# MultiGRADE_control_panel_V01_R1.net
KiCad netlist of a schematic drawn in EAGLE
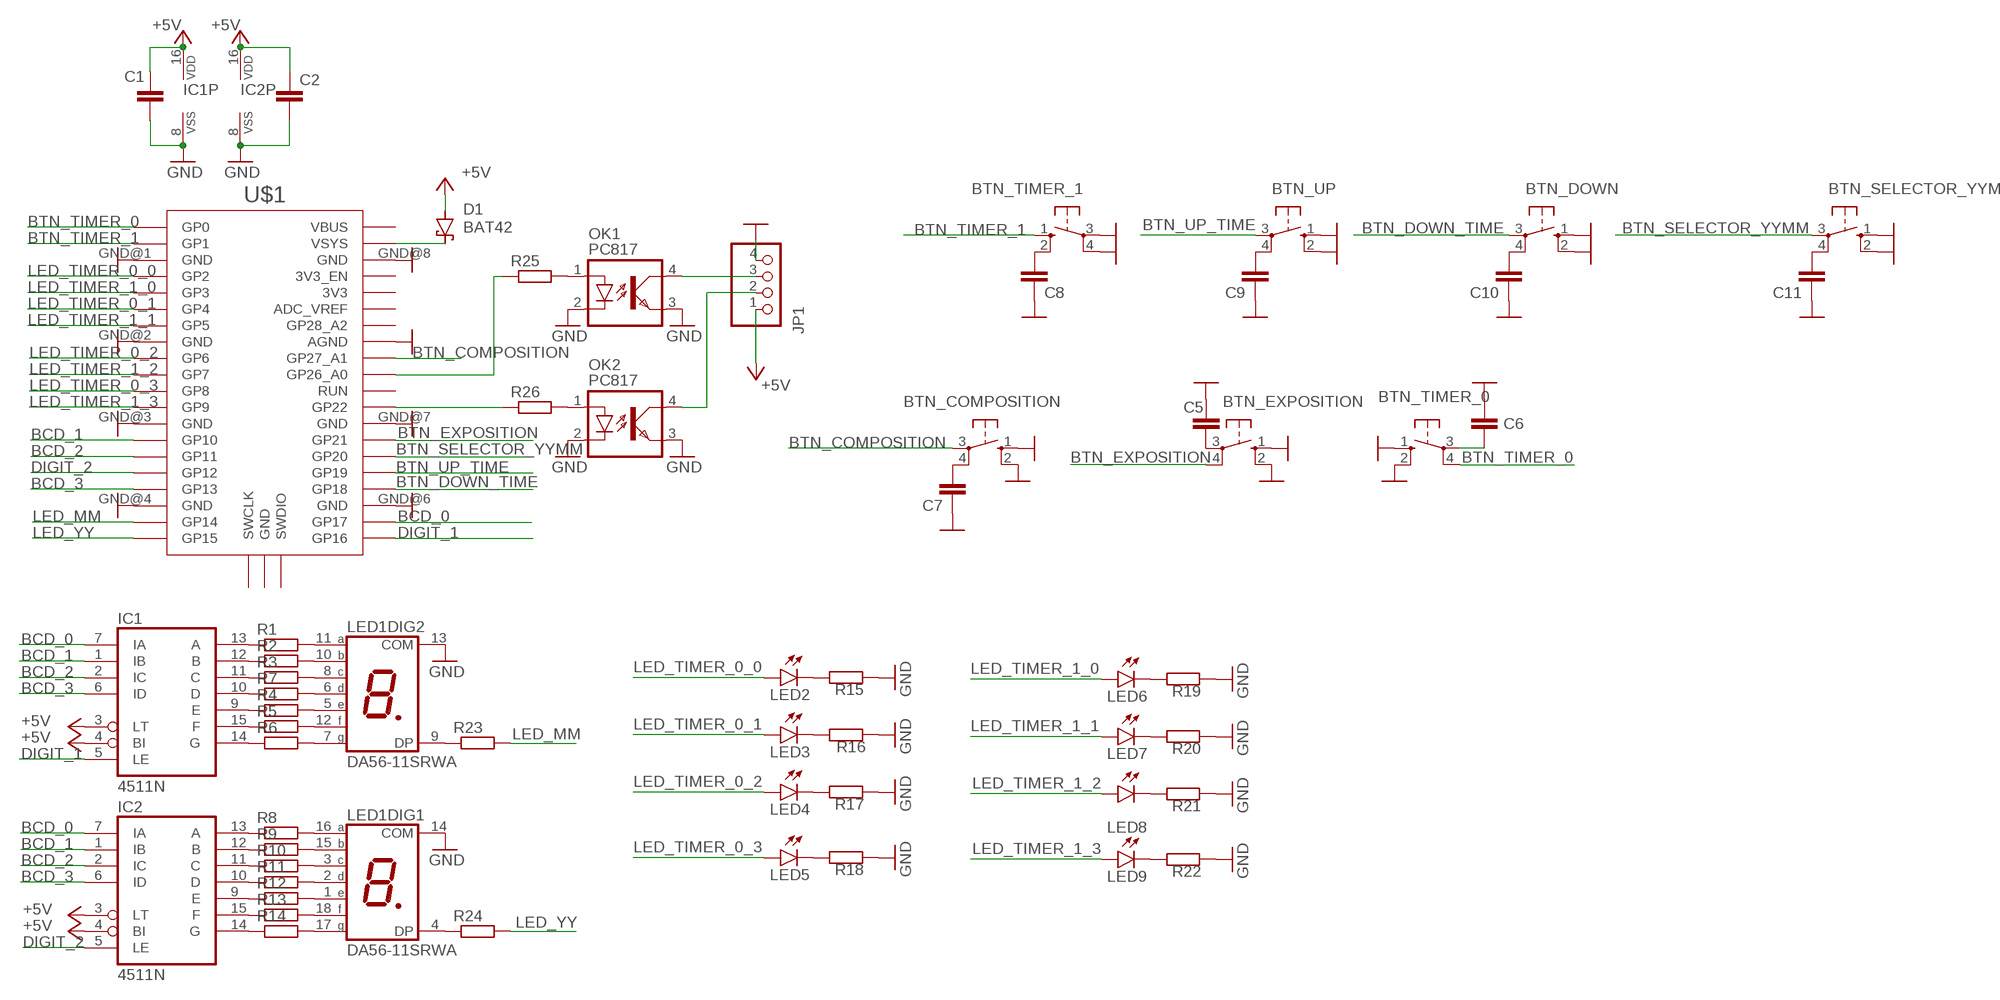
[diagram p0: schematic, sheet 1]

(export (version "E")
  (design (tool "Eeschema 10.0.6"))
  (components
    (comp (ref "BTN_COMPOSITION")
      (value "10-XX")
      (footprint "eagle-import:B3F-10XX")
      (fields (field (name "MPN") "B3F-1000"))
      (libsource (lib "eagle-import") (part "10-XX"))
    )
    (comp (ref "BTN_DOWN")
      (value "10-XX")
      (footprint "eagle-import:B3F-10XX")
      (fields (field (name "MPN") "B3F-1000"))
      (libsource (lib "eagle-import") (part "10-XX"))
    )
    (comp (ref "BTN_EXPOSITION")
      (value "10-XX")
      (footprint "eagle-import:B3F-10XX")
      (fields (field (name "MPN") "B3F-1000"))
      (libsource (lib "eagle-import") (part "10-XX"))
    )
    (comp (ref "BTN_SELECTOR_YYMM")
      (value "10-XX")
      (footprint "eagle-import:B3F-10XX")
      (fields (field (name "MPN") "B3F-1000"))
      (libsource (lib "eagle-import") (part "10-XX"))
    )
    (comp (ref "BTN_TIMER_0")
      (value "10-XX")
      (footprint "eagle-import:B3F-10XX")
      (fields (field (name "MPN") "B3F-1000"))
      (libsource (lib "eagle-import") (part "10-XX"))
    )
    (comp (ref "BTN_TIMER_1")
      (value "10-XX")
      (footprint "eagle-import:B3F-10XX")
      (fields (field (name "MPN") "B3F-1000"))
      (libsource (lib "eagle-import") (part "10-XX"))
    )
    (comp (ref "BTN_UP")
      (value "10-XX")
      (footprint "eagle-import:B3F-10XX")
      (fields (field (name "MPN") "B3F-1000"))
      (libsource (lib "eagle-import") (part "10-XX"))
    )
    (comp (ref "C1")
      (value "C-EU050-025X075")
      (footprint "eagle-import:C050-025X075")
      (libsource (lib "eagle-import") (part "C-EU050-025X075"))
    )
    (comp (ref "C2")
      (value "C-EU050-025X075")
      (footprint "eagle-import:C050-025X075")
      (libsource (lib "eagle-import") (part "C-EU050-025X075"))
    )
    (comp (ref "C5")
      (value "C-EU025-025X050")
      (footprint "eagle-import:C025-025X050")
      (libsource (lib "eagle-import") (part "C-EU025-025X050"))
    )
    (comp (ref "C6")
      (value "C-EU025-025X050")
      (footprint "eagle-import:C025-025X050")
      (libsource (lib "eagle-import") (part "C-EU025-025X050"))
    )
    (comp (ref "C7")
      (value "C-EU025-025X050")
      (footprint "eagle-import:C025-025X050")
      (libsource (lib "eagle-import") (part "C-EU025-025X050"))
    )
    (comp (ref "C8")
      (value "C-EU025-025X050")
      (footprint "eagle-import:C025-025X050")
      (libsource (lib "eagle-import") (part "C-EU025-025X050"))
    )
    (comp (ref "C9")
      (value "C-EU025-025X050")
      (footprint "eagle-import:C025-025X050")
      (libsource (lib "eagle-import") (part "C-EU025-025X050"))
    )
    (comp (ref "C10")
      (value "C-EU025-025X050")
      (footprint "eagle-import:C025-025X050")
      (libsource (lib "eagle-import") (part "C-EU025-025X050"))
    )
    (comp (ref "C11")
      (value "C-EU025-025X050")
      (footprint "eagle-import:C025-025X050")
      (libsource (lib "eagle-import") (part "C-EU025-025X050"))
    )
    (comp (ref "D1")
      (value "BAT42")
      (footprint "eagle-import:DO35-10")
      (libsource (lib "eagle-import") (part "BAT42"))
    )
    (comp (ref "IC1")
      (value "4511N")
      (footprint "eagle-import:DIL16")
      (libsource (lib "eagle-import") (part "4511N"))
    )
    (comp (ref "IC2")
      (value "4511N")
      (footprint "eagle-import:DIL16")
      (libsource (lib "eagle-import") (part "4511N"))
    )
    (comp (ref "JP1")
      (value "PINHD-1X4")
      (footprint "eagle-import:1X04")
      (libsource (lib "eagle-import") (part "PINHD-1X4"))
    )
    (comp (ref "LED1")
      (value "DA56-11SRWA")
      (footprint "eagle-import:DA56")
      (libsource (lib "eagle-import") (part "DA56-11SRWA"))
    )
    (comp (ref "LED2")
      (value "LED3MM")
      (footprint "eagle-import:LED3MM")
      (libsource (lib "eagle-import") (part "LED3MM"))
    )
    (comp (ref "LED3")
      (value "LED3MM")
      (footprint "eagle-import:LED3MM")
      (libsource (lib "eagle-import") (part "LED3MM"))
    )
    (comp (ref "LED4")
      (value "LED3MM")
      (footprint "eagle-import:LED3MM")
      (libsource (lib "eagle-import") (part "LED3MM"))
    )
    (comp (ref "LED5")
      (value "LED3MM")
      (footprint "eagle-import:LED3MM")
      (libsource (lib "eagle-import") (part "LED3MM"))
    )
    (comp (ref "LED6")
      (value "LED3MM")
      (footprint "eagle-import:LED3MM")
      (libsource (lib "eagle-import") (part "LED3MM"))
    )
    (comp (ref "LED7")
      (value "LED3MM")
      (footprint "eagle-import:LED3MM")
      (libsource (lib "eagle-import") (part "LED3MM"))
    )
    (comp (ref "LED8")
      (value "LED3MM")
      (footprint "eagle-import:LED3MM")
      (libsource (lib "eagle-import") (part "LED3MM"))
    )
    (comp (ref "LED9")
      (value "LED3MM")
      (footprint "eagle-import:LED3MM")
      (libsource (lib "eagle-import") (part "LED3MM"))
    )
    (comp (ref "OK1")
      (value "PC817")
      (footprint "eagle-import:DIL04")
      (fields (field (name "MPN") "PC817X4J000F"))
      (libsource (lib "eagle-import") (part "PC817"))
    )
    (comp (ref "OK2")
      (value "PC817")
      (footprint "eagle-import:DIL04")
      (fields (field (name "MPN") "PC817X4J000F"))
      (libsource (lib "eagle-import") (part "PC817"))
    )
    (comp (ref "R1")
      (value "R-EU_0204/7")
      (footprint "eagle-import:0204_7")
      (libsource (lib "eagle-import") (part "R-EU_0204/7"))
    )
    (comp (ref "R2")
      (value "R-EU_0204/7")
      (footprint "eagle-import:0204_7")
      (libsource (lib "eagle-import") (part "R-EU_0204/7"))
    )
    (comp (ref "R3")
      (value "R-EU_0204/7")
      (footprint "eagle-import:0204_7")
      (libsource (lib "eagle-import") (part "R-EU_0204/7"))
    )
    (comp (ref "R4")
      (value "R-EU_0204/7")
      (footprint "eagle-import:0204_7")
      (libsource (lib "eagle-import") (part "R-EU_0204/7"))
    )
    (comp (ref "R5")
      (value "R-EU_0204/7")
      (footprint "eagle-import:0204_7")
      (libsource (lib "eagle-import") (part "R-EU_0204/7"))
    )
    (comp (ref "R6")
      (value "R-EU_0204/7")
      (footprint "eagle-import:0204_7")
      (libsource (lib "eagle-import") (part "R-EU_0204/7"))
    )
    (comp (ref "R7")
      (value "R-EU_0204/7")
      (footprint "eagle-import:0204_7")
      (libsource (lib "eagle-import") (part "R-EU_0204/7"))
    )
    (comp (ref "R8")
      (value "R-EU_0204/7")
      (footprint "eagle-import:0204_7")
      (libsource (lib "eagle-import") (part "R-EU_0204/7"))
    )
    (comp (ref "R9")
      (value "R-EU_0204/7")
      (footprint "eagle-import:0204_7")
      (libsource (lib "eagle-import") (part "R-EU_0204/7"))
    )
    (comp (ref "R10")
      (value "R-EU_0204/7")
      (footprint "eagle-import:0204_7")
      (libsource (lib "eagle-import") (part "R-EU_0204/7"))
    )
    (comp (ref "R11")
      (value "R-EU_0204/7")
      (footprint "eagle-import:0204_7")
      (libsource (lib "eagle-import") (part "R-EU_0204/7"))
    )
    (comp (ref "R12")
      (value "R-EU_0204/7")
      (footprint "eagle-import:0204_7")
      (libsource (lib "eagle-import") (part "R-EU_0204/7"))
    )
    (comp (ref "R13")
      (value "R-EU_0204/7")
      (footprint "eagle-import:0204_7")
      (libsource (lib "eagle-import") (part "R-EU_0204/7"))
    )
    (comp (ref "R14")
      (value "R-EU_0204/7")
      (footprint "eagle-import:0204_7")
      (libsource (lib "eagle-import") (part "R-EU_0204/7"))
    )
    (comp (ref "R15")
      (value "R-EU_0204/7")
      (footprint "eagle-import:0204_7")
      (libsource (lib "eagle-import") (part "R-EU_0204/7"))
    )
    (comp (ref "R16")
      (value "R-EU_0204/7")
      (footprint "eagle-import:0204_7")
      (libsource (lib "eagle-import") (part "R-EU_0204/7"))
    )
    (comp (ref "R17")
      (value "R-EU_0204/7")
      (footprint "eagle-import:0204_7")
      (libsource (lib "eagle-import") (part "R-EU_0204/7"))
    )
    (comp (ref "R18")
      (value "R-EU_0204/7")
      (footprint "eagle-import:0204_7")
      (libsource (lib "eagle-import") (part "R-EU_0204/7"))
    )
    (comp (ref "R19")
      (value "R-EU_0204/7")
      (footprint "eagle-import:0204_7")
      (libsource (lib "eagle-import") (part "R-EU_0204/7"))
    )
    (comp (ref "R20")
      (value "R-EU_0204/7")
      (footprint "eagle-import:0204_7")
      (libsource (lib "eagle-import") (part "R-EU_0204/7"))
    )
    (comp (ref "R21")
      (value "R-EU_0204/7")
      (footprint "eagle-import:0204_7")
      (libsource (lib "eagle-import") (part "R-EU_0204/7"))
    )
    (comp (ref "R22")
      (value "R-EU_0204/7")
      (footprint "eagle-import:0204_7")
      (libsource (lib "eagle-import") (part "R-EU_0204/7"))
    )
    (comp (ref "R23")
      (value "R-EU_0204/7")
      (footprint "eagle-import:0204_7")
      (libsource (lib "eagle-import") (part "R-EU_0204/7"))
    )
    (comp (ref "R24")
      (value "R-EU_0204/7")
      (footprint "eagle-import:0204_7")
      (libsource (lib "eagle-import") (part "R-EU_0204/7"))
    )
    (comp (ref "R25")
      (value "R-EU_0204/7")
      (footprint "eagle-import:0204_7")
      (libsource (lib "eagle-import") (part "R-EU_0204/7"))
    )
    (comp (ref "R26")
      (value "R-EU_0204/7")
      (footprint "eagle-import:0204_7")
      (libsource (lib "eagle-import") (part "R-EU_0204/7"))
    )
    (comp (ref "U$1")
      (value "RPI_PICO_IG-TH")
      (footprint "eagle-import:RPI_PICO_TH")
      (libsource (lib "eagle-import") (part "RPI_PICO_IG-TH"))
    )
  )
  (nets
    (net (code "1") (name "+5V") (class "Default")
      (node (ref "C1") (pin "1") (pinfunction "1_1") (pintype "passive"))
      (node (ref "C2") (pin "1") (pinfunction "1_1") (pintype "passive"))
      (node (ref "D1") (pin "A") (pinfunction "A_A") (pintype "passive"))
      (node (ref "IC1") (pin "16") (pinfunction "VDD_16") (pintype "power_in"))
      (node (ref "IC1") (pin "3") (pinfunction "LT_3") (pintype "input"))
      (node (ref "IC1") (pin "4") (pinfunction "BI_4") (pintype "input"))
      (node (ref "IC2") (pin "16") (pinfunction "VDD_16") (pintype "power_in"))
      (node (ref "IC2") (pin "3") (pinfunction "LT_3") (pintype "input"))
      (node (ref "IC2") (pin "4") (pinfunction "BI_4") (pintype "input"))
      (node (ref "JP1") (pin "1") (pinfunction "1_1") (pintype "passive"))
    )
    (net (code "2") (name "/BCD_0") (class "Default")
      (node (ref "IC1") (pin "7") (pinfunction "IA_7") (pintype "input"))
      (node (ref "IC2") (pin "7") (pinfunction "IA_7") (pintype "input"))
      (node (ref "U$1") (pin "GP17") (pinfunction "GP17_GP17") (pintype "bidirectional"))
    )
    (net (code "3") (name "/BCD_1") (class "Default")
      (node (ref "IC1") (pin "1") (pinfunction "IB_1") (pintype "input"))
      (node (ref "IC2") (pin "1") (pinfunction "IB_1") (pintype "input"))
      (node (ref "U$1") (pin "GP10") (pinfunction "GP10_GP10") (pintype "bidirectional"))
    )
    (net (code "4") (name "/BCD_2") (class "Default")
      (node (ref "IC1") (pin "2") (pinfunction "IC_2") (pintype "input"))
      (node (ref "IC2") (pin "2") (pinfunction "IC_2") (pintype "input"))
      (node (ref "U$1") (pin "GP11") (pinfunction "GP11_GP11") (pintype "bidirectional"))
    )
    (net (code "5") (name "/BCD_3") (class "Default")
      (node (ref "IC1") (pin "6") (pinfunction "ID_6") (pintype "input"))
      (node (ref "IC2") (pin "6") (pinfunction "ID_6") (pintype "input"))
      (node (ref "U$1") (pin "GP13") (pinfunction "GP13_GP13") (pintype "bidirectional"))
    )
    (net (code "6") (name "/BTN_COMPOSITION") (class "Default")
      (node (ref "BTN_COMPOSITION") (pin "3") (pinfunction "P_3") (pintype "passive"))
      (node (ref "U$1") (pin "GP27_A1") (pinfunction "GP27_A1_GP27_A1") (pintype "bidirectional"))
    )
    (net (code "7") (name "/BTN_DOWN_TIME") (class "Default")
      (node (ref "BTN_DOWN") (pin "3") (pinfunction "P_3") (pintype "passive"))
      (node (ref "U$1") (pin "GP18") (pinfunction "GP18_GP18") (pintype "bidirectional"))
    )
    (net (code "8") (name "/BTN_EXPOSITION") (class "Default")
      (node (ref "BTN_EXPOSITION") (pin "4") (pinfunction "P1_4") (pintype "passive"))
      (node (ref "U$1") (pin "GP21") (pinfunction "GP21_GP21") (pintype "bidirectional"))
    )
    (net (code "9") (name "/BTN_SELECTOR_YYMM") (class "Default")
      (node (ref "BTN_SELECTOR_YYMM") (pin "3") (pinfunction "P_3") (pintype "passive"))
      (node (ref "U$1") (pin "GP20") (pinfunction "GP20_GP20") (pintype "bidirectional"))
    )
    (net (code "10") (name "/BTN_TIMER_0") (class "Default")
      (node (ref "BTN_TIMER_0") (pin "4") (pinfunction "P1_4") (pintype "passive"))
      (node (ref "U$1") (pin "GP0") (pinfunction "GP0_GP0") (pintype "bidirectional"))
    )
    (net (code "11") (name "/BTN_TIMER_1") (class "Default")
      (node (ref "BTN_TIMER_1") (pin "1") (pinfunction "S_1") (pintype "passive"))
      (node (ref "U$1") (pin "GP1") (pinfunction "GP1_GP1") (pintype "bidirectional"))
    )
    (net (code "12") (name "/BTN_UP_TIME") (class "Default")
      (node (ref "BTN_UP") (pin "3") (pinfunction "P_3") (pintype "passive"))
      (node (ref "U$1") (pin "GP19") (pinfunction "GP19_GP19") (pintype "bidirectional"))
    )
    (net (code "13") (name "/DIGIT_1") (class "Default")
      (node (ref "IC1") (pin "5") (pinfunction "LE_5") (pintype "input"))
      (node (ref "U$1") (pin "GP16") (pinfunction "GP16_GP16") (pintype "bidirectional"))
    )
    (net (code "14") (name "/DIGIT_2") (class "Default")
      (node (ref "IC2") (pin "5") (pinfunction "LE_5") (pintype "input"))
      (node (ref "U$1") (pin "GP12") (pinfunction "GP12_GP12") (pintype "bidirectional"))
    )
    (net (code "15") (name "/LED_MM") (class "Default")
      (node (ref "R23") (pin "2") (pinfunction "2_2") (pintype "passive"))
      (node (ref "U$1") (pin "GP14") (pinfunction "GP14_GP14") (pintype "bidirectional"))
    )
    (net (code "16") (name "/LED_TIMER_0_0") (class "Default")
      (node (ref "LED2") (pin "A") (pinfunction "A_A") (pintype "passive"))
      (node (ref "U$1") (pin "GP2") (pinfunction "GP2_GP2") (pintype "bidirectional"))
    )
    (net (code "17") (name "/LED_TIMER_0_1") (class "Default")
      (node (ref "LED3") (pin "A") (pinfunction "A_A") (pintype "passive"))
      (node (ref "U$1") (pin "GP4") (pinfunction "GP4_GP4") (pintype "bidirectional"))
    )
    (net (code "18") (name "/LED_TIMER_0_2") (class "Default")
      (node (ref "LED4") (pin "A") (pinfunction "A_A") (pintype "passive"))
      (node (ref "U$1") (pin "GP6") (pinfunction "GP6_GP6") (pintype "bidirectional"))
    )
    (net (code "19") (name "/LED_TIMER_0_3") (class "Default")
      (node (ref "LED5") (pin "A") (pinfunction "A_A") (pintype "passive"))
      (node (ref "U$1") (pin "GP8") (pinfunction "GP8_GP8") (pintype "bidirectional"))
    )
    (net (code "20") (name "/LED_TIMER_1_0") (class "Default")
      (node (ref "LED6") (pin "A") (pinfunction "A_A") (pintype "passive"))
      (node (ref "U$1") (pin "GP3") (pinfunction "GP3_GP3") (pintype "bidirectional"))
    )
    (net (code "21") (name "/LED_TIMER_1_1") (class "Default")
      (node (ref "LED7") (pin "A") (pinfunction "A_A") (pintype "passive"))
      (node (ref "U$1") (pin "GP5") (pinfunction "GP5_GP5") (pintype "bidirectional"))
    )
    (net (code "22") (name "/LED_TIMER_1_2") (class "Default")
      (node (ref "LED8") (pin "A") (pinfunction "A_A") (pintype "passive"))
      (node (ref "U$1") (pin "GP7") (pinfunction "GP7_GP7") (pintype "bidirectional"))
    )
    (net (code "23") (name "/LED_TIMER_1_3") (class "Default")
      (node (ref "LED9") (pin "A") (pinfunction "A_A") (pintype "passive"))
      (node (ref "U$1") (pin "GP9") (pinfunction "GP9_GP9") (pintype "bidirectional"))
    )
    (net (code "24") (name "/LED_YY") (class "Default")
      (node (ref "R24") (pin "2") (pinfunction "2_2") (pintype "passive"))
      (node (ref "U$1") (pin "GP15") (pinfunction "GP15_GP15") (pintype "bidirectional"))
    )
    (net (code "25") (name "GND") (class "Default")
      (node (ref "BTN_COMPOSITION") (pin "1") (pinfunction "S_1") (pintype "passive"))
      (node (ref "BTN_COMPOSITION") (pin "2") (pinfunction "S1_2") (pintype "passive"))
      (node (ref "BTN_DOWN") (pin "1") (pinfunction "S_1") (pintype "passive"))
      (node (ref "BTN_DOWN") (pin "2") (pinfunction "S1_2") (pintype "passive"))
      (node (ref "BTN_EXPOSITION") (pin "1") (pinfunction "S_1") (pintype "passive"))
      (node (ref "BTN_EXPOSITION") (pin "2") (pinfunction "S1_2") (pintype "passive"))
      (node (ref "BTN_SELECTOR_YYMM") (pin "1") (pinfunction "S_1") (pintype "passive"))
      (node (ref "BTN_SELECTOR_YYMM") (pin "2") (pinfunction "S1_2") (pintype "passive"))
      (node (ref "BTN_TIMER_0") (pin "1") (pinfunction "S_1") (pintype "passive"))
      (node (ref "BTN_TIMER_0") (pin "2") (pinfunction "S1_2") (pintype "passive"))
      (node (ref "BTN_TIMER_1") (pin "3") (pinfunction "P_3") (pintype "passive"))
      (node (ref "BTN_TIMER_1") (pin "4") (pinfunction "P1_4") (pintype "passive"))
      (node (ref "BTN_UP") (pin "1") (pinfunction "S_1") (pintype "passive"))
      (node (ref "BTN_UP") (pin "2") (pinfunction "S1_2") (pintype "passive"))
      (node (ref "C1") (pin "2") (pinfunction "2_2") (pintype "passive"))
      (node (ref "C10") (pin "1") (pinfunction "1_1") (pintype "passive"))
      (node (ref "C11") (pin "1") (pinfunction "1_1") (pintype "passive"))
      (node (ref "C2") (pin "2") (pinfunction "2_2") (pintype "passive"))
      (node (ref "C5") (pin "1") (pinfunction "1_1") (pintype "passive"))
      (node (ref "C6") (pin "1") (pinfunction "1_1") (pintype "passive"))
      (node (ref "C7") (pin "1") (pinfunction "1_1") (pintype "passive"))
      (node (ref "C8") (pin "1") (pinfunction "1_1") (pintype "passive"))
      (node (ref "C9") (pin "1") (pinfunction "1_1") (pintype "passive"))
      (node (ref "IC1") (pin "8") (pinfunction "VSS_8") (pintype "power_in"))
      (node (ref "IC2") (pin "8") (pinfunction "VSS_8") (pintype "power_in"))
      (node (ref "JP1") (pin "4") (pinfunction "4_4") (pintype "passive"))
      (node (ref "LED1") (pin "13") (pinfunction "COM_13") (pintype "passive"))
      (node (ref "LED1") (pin "14") (pinfunction "COM_14") (pintype "passive"))
      (node (ref "OK1") (pin "2") (pinfunction "C_2") (pintype "passive"))
      (node (ref "OK1") (pin "3") (pinfunction "EMIT_3") (pintype "passive"))
      (node (ref "OK2") (pin "2") (pinfunction "C_2") (pintype "passive"))
      (node (ref "OK2") (pin "3") (pinfunction "EMIT_3") (pintype "passive"))
      (node (ref "R15") (pin "1") (pinfunction "1_1") (pintype "passive"))
      (node (ref "R16") (pin "1") (pinfunction "1_1") (pintype "passive"))
      (node (ref "R17") (pin "1") (pinfunction "1_1") (pintype "passive"))
      (node (ref "R18") (pin "1") (pinfunction "1_1") (pintype "passive"))
      (node (ref "R19") (pin "1") (pinfunction "1_1") (pintype "passive"))
      (node (ref "R20") (pin "1") (pinfunction "1_1") (pintype "passive"))
      (node (ref "R21") (pin "1") (pinfunction "1_1") (pintype "passive"))
      (node (ref "R22") (pin "1") (pinfunction "1_1") (pintype "passive"))
      (node (ref "U$1") (pin "AGND") (pinfunction "AGND_AGND") (pintype "bidirectional"))
      (node (ref "U$1") (pin "GND@1") (pinfunction "GND_GND@1") (pintype "bidirectional"))
      (node (ref "U$1") (pin "GND@2") (pinfunction "GND_GND@2") (pintype "bidirectional"))
      (node (ref "U$1") (pin "GND@3") (pinfunction "GND_GND@3") (pintype "bidirectional"))
      (node (ref "U$1") (pin "GND@4") (pinfunction "GND_GND@4") (pintype "bidirectional"))
      (node (ref "U$1") (pin "GND@6") (pinfunction "GND_GND@6") (pintype "bidirectional"))
      (node (ref "U$1") (pin "GND@7") (pinfunction "GND_GND@7") (pintype "bidirectional"))
      (node (ref "U$1") (pin "GND@8") (pinfunction "GND_GND@8") (pintype "bidirectional"))
    )
    (net (code "26") (name "Net-(BTN_COMPOSITION-P1)") (class "Default")
      (node (ref "BTN_COMPOSITION") (pin "4") (pinfunction "P1_4") (pintype "passive"))
      (node (ref "C7") (pin "2") (pinfunction "2_2") (pintype "passive"))
    )
    (net (code "27") (name "Net-(BTN_DOWN-P1)") (class "Default")
      (node (ref "BTN_DOWN") (pin "4") (pinfunction "P1_4") (pintype "passive"))
      (node (ref "C10") (pin "2") (pinfunction "2_2") (pintype "passive"))
    )
    (net (code "28") (name "Net-(BTN_EXPOSITION-P)") (class "Default")
      (node (ref "BTN_EXPOSITION") (pin "3") (pinfunction "P_3") (pintype "passive"))
      (node (ref "C5") (pin "2") (pinfunction "2_2") (pintype "passive"))
    )
    (net (code "29") (name "Net-(BTN_SELECTOR_YYMM-P1)") (class "Default")
      (node (ref "BTN_SELECTOR_YYMM") (pin "4") (pinfunction "P1_4") (pintype "passive"))
      (node (ref "C11") (pin "2") (pinfunction "2_2") (pintype "passive"))
    )
    (net (code "30") (name "Net-(BTN_TIMER_0-P)") (class "Default")
      (node (ref "BTN_TIMER_0") (pin "3") (pinfunction "P_3") (pintype "passive"))
      (node (ref "C6") (pin "2") (pinfunction "2_2") (pintype "passive"))
    )
    (net (code "31") (name "Net-(BTN_TIMER_1-S1)") (class "Default")
      (node (ref "BTN_TIMER_1") (pin "2") (pinfunction "S1_2") (pintype "passive"))
      (node (ref "C8") (pin "2") (pinfunction "2_2") (pintype "passive"))
    )
    (net (code "32") (name "Net-(BTN_UP-P1)") (class "Default")
      (node (ref "BTN_UP") (pin "4") (pinfunction "P1_4") (pintype "passive"))
      (node (ref "C9") (pin "2") (pinfunction "2_2") (pintype "passive"))
    )
    (net (code "33") (name "Net-(D1-PadC)") (class "Default")
      (node (ref "D1") (pin "C") (pinfunction "C_C") (pintype "passive"))
      (node (ref "U$1") (pin "VSYS") (pinfunction "VSYS_VSYS") (pintype "bidirectional"))
    )
    (net (code "34") (name "Net-(IC1A-A)") (class "Default")
      (node (ref "IC1") (pin "13") (pinfunction "A_13") (pintype "output"))
      (node (ref "R1") (pin "1") (pinfunction "1_1") (pintype "passive"))
    )
    (net (code "35") (name "Net-(IC1A-B)") (class "Default")
      (node (ref "IC1") (pin "12") (pinfunction "B_12") (pintype "output"))
      (node (ref "R2") (pin "1") (pinfunction "1_1") (pintype "passive"))
    )
    (net (code "36") (name "Net-(IC1A-C)") (class "Default")
      (node (ref "IC1") (pin "11") (pinfunction "C_11") (pintype "output"))
      (node (ref "R3") (pin "1") (pinfunction "1_1") (pintype "passive"))
    )
    (net (code "37") (name "Net-(IC1A-D)") (class "Default")
      (node (ref "IC1") (pin "10") (pinfunction "D_10") (pintype "output"))
      (node (ref "R7") (pin "1") (pinfunction "1_1") (pintype "passive"))
    )
    (net (code "38") (name "Net-(IC1A-E)") (class "Default")
      (node (ref "IC1") (pin "9") (pinfunction "E_9") (pintype "output"))
      (node (ref "R4") (pin "1") (pinfunction "1_1") (pintype "passive"))
    )
    (net (code "39") (name "Net-(IC1A-F)") (class "Default")
      (node (ref "IC1") (pin "15") (pinfunction "F_15") (pintype "output"))
      (node (ref "R5") (pin "1") (pinfunction "1_1") (pintype "passive"))
    )
    (net (code "40") (name "Net-(IC1A-G)") (class "Default")
      (node (ref "IC1") (pin "14") (pinfunction "G_14") (pintype "output"))
      (node (ref "R6") (pin "1") (pinfunction "1_1") (pintype "passive"))
    )
    (net (code "41") (name "Net-(IC2A-A)") (class "Default")
      (node (ref "IC2") (pin "13") (pinfunction "A_13") (pintype "output"))
      (node (ref "R8") (pin "1") (pinfunction "1_1") (pintype "passive"))
    )
    (net (code "42") (name "Net-(IC2A-B)") (class "Default")
      (node (ref "IC2") (pin "12") (pinfunction "B_12") (pintype "output"))
      (node (ref "R9") (pin "1") (pinfunction "1_1") (pintype "passive"))
    )
    (net (code "43") (name "Net-(IC2A-C)") (class "Default")
      (node (ref "IC2") (pin "11") (pinfunction "C_11") (pintype "output"))
      (node (ref "R10") (pin "1") (pinfunction "1_1") (pintype "passive"))
    )
    (net (code "44") (name "Net-(IC2A-D)") (class "Default")
      (node (ref "IC2") (pin "10") (pinfunction "D_10") (pintype "output"))
      (node (ref "R11") (pin "1") (pinfunction "1_1") (pintype "passive"))
    )
    (net (code "45") (name "Net-(IC2A-E)") (class "Default")
      (node (ref "IC2") (pin "9") (pinfunction "E_9") (pintype "output"))
      (node (ref "R12") (pin "1") (pinfunction "1_1") (pintype "passive"))
    )
    (net (code "46") (name "Net-(IC2A-F)") (class "Default")
      (node (ref "IC2") (pin "15") (pinfunction "F_15") (pintype "output"))
      (node (ref "R13") (pin "1") (pinfunction "1_1") (pintype "passive"))
    )
    (net (code "47") (name "Net-(IC2A-G)") (class "Default")
      (node (ref "IC2") (pin "14") (pinfunction "G_14") (pintype "output"))
      (node (ref "R14") (pin "1") (pinfunction "1_1") (pintype "passive"))
    )
    (net (code "48") (name "Net-(LED1A-A)") (class "Default")
      (node (ref "LED1") (pin "16") (pinfunction "A_16") (pintype "passive"))
      (node (ref "R8") (pin "2") (pinfunction "2_2") (pintype "passive"))
    )
    (net (code "49") (name "Net-(LED1A-B)") (class "Default")
      (node (ref "LED1") (pin "15") (pinfunction "B_15") (pintype "passive"))
      (node (ref "R9") (pin "2") (pinfunction "2_2") (pintype "passive"))
    )
    (net (code "50") (name "Net-(LED1A-C)") (class "Default")
      (node (ref "LED1") (pin "3") (pinfunction "C_3") (pintype "passive"))
      (node (ref "R10") (pin "2") (pinfunction "2_2") (pintype "passive"))
    )
    (net (code "51") (name "Net-(LED1A-D)") (class "Default")
      (node (ref "LED1") (pin "2") (pinfunction "D_2") (pintype "passive"))
      (node (ref "R11") (pin "2") (pinfunction "2_2") (pintype "passive"))
    )
    (net (code "52") (name "Net-(LED1A-DP)") (class "Default")
      (node (ref "LED1") (pin "4") (pinfunction "DP_4") (pintype "passive"))
      (node (ref "R24") (pin "1") (pinfunction "1_1") (pintype "passive"))
    )
    (net (code "53") (name "Net-(LED1A-E)") (class "Default")
      (node (ref "LED1") (pin "1") (pinfunction "E_1") (pintype "passive"))
      (node (ref "R12") (pin "2") (pinfunction "2_2") (pintype "passive"))
    )
    (net (code "54") (name "Net-(LED1A-F)") (class "Default")
      (node (ref "LED1") (pin "18") (pinfunction "F_18") (pintype "passive"))
      (node (ref "R13") (pin "2") (pinfunction "2_2") (pintype "passive"))
    )
    (net (code "55") (name "Net-(LED1A-G)") (class "Default")
      (node (ref "LED1") (pin "17") (pinfunction "G_17") (pintype "passive"))
      (node (ref "R14") (pin "2") (pinfunction "2_2") (pintype "passive"))
    )
    (net (code "56") (name "Net-(LED1B-A)") (class "Default")
      (node (ref "LED1") (pin "11") (pinfunction "A_11") (pintype "passive"))
      (node (ref "R1") (pin "2") (pinfunction "2_2") (pintype "passive"))
    )
    (net (code "57") (name "Net-(LED1B-B)") (class "Default")
      (node (ref "LED1") (pin "10") (pinfunction "B_10") (pintype "passive"))
      (node (ref "R2") (pin "2") (pinfunction "2_2") (pintype "passive"))
    )
    (net (code "58") (name "Net-(LED1B-C)") (class "Default")
      (node (ref "LED1") (pin "8") (pinfunction "C_8") (pintype "passive"))
      (node (ref "R3") (pin "2") (pinfunction "2_2") (pintype "passive"))
    )
    (net (code "59") (name "Net-(LED1B-D)") (class "Default")
      (node (ref "LED1") (pin "6") (pinfunction "D_6") (pintype "passive"))
      (node (ref "R7") (pin "2") (pinfunction "2_2") (pintype "passive"))
    )
    (net (code "60") (name "Net-(LED1B-DP)") (class "Default")
      (node (ref "LED1") (pin "9") (pinfunction "DP_9") (pintype "passive"))
      (node (ref "R23") (pin "1") (pinfunction "1_1") (pintype "passive"))
    )
    (net (code "61") (name "Net-(LED1B-E)") (class "Default")
      (node (ref "LED1") (pin "5") (pinfunction "E_5") (pintype "passive"))
      (node (ref "R4") (pin "2") (pinfunction "2_2") (pintype "passive"))
    )
    (net (code "62") (name "Net-(LED1B-F)") (class "Default")
      (node (ref "LED1") (pin "12") (pinfunction "F_12") (pintype "passive"))
      (node (ref "R5") (pin "2") (pinfunction "2_2") (pintype "passive"))
    )
    (net (code "63") (name "Net-(LED1B-G)") (class "Default")
      (node (ref "LED1") (pin "7") (pinfunction "G_7") (pintype "passive"))
      (node (ref "R6") (pin "2") (pinfunction "2_2") (pintype "passive"))
    )
    (net (code "64") (name "Net-(LED2-C)") (class "Default")
      (node (ref "LED2") (pin "K") (pinfunction "C_K") (pintype "passive"))
      (node (ref "R15") (pin "2") (pinfunction "2_2") (pintype "passive"))
    )
    (net (code "65") (name "Net-(LED3-C)") (class "Default")
      (node (ref "LED3") (pin "K") (pinfunction "C_K") (pintype "passive"))
      (node (ref "R16") (pin "2") (pinfunction "2_2") (pintype "passive"))
    )
    (net (code "66") (name "Net-(LED4-C)") (class "Default")
      (node (ref "LED4") (pin "K") (pinfunction "C_K") (pintype "passive"))
      (node (ref "R17") (pin "2") (pinfunction "2_2") (pintype "passive"))
    )
    (net (code "67") (name "Net-(LED5-C)") (class "Default")
      (node (ref "LED5") (pin "K") (pinfunction "C_K") (pintype "passive"))
      (node (ref "R18") (pin "2") (pinfunction "2_2") (pintype "passive"))
    )
    (net (code "68") (name "Net-(LED6-C)") (class "Default")
      (node (ref "LED6") (pin "K") (pinfunction "C_K") (pintype "passive"))
      (node (ref "R19") (pin "2") (pinfunction "2_2") (pintype "passive"))
    )
    (net (code "69") (name "Net-(LED7-C)") (class "Default")
      (node (ref "LED7") (pin "K") (pinfunction "C_K") (pintype "passive"))
      (node (ref "R20") (pin "2") (pinfunction "2_2") (pintype "passive"))
    )
    (net (code "70") (name "Net-(LED8-C)") (class "Default")
      (node (ref "LED8") (pin "K") (pinfunction "C_K") (pintype "passive"))
      (node (ref "R21") (pin "2") (pinfunction "2_2") (pintype "passive"))
    )
    (net (code "71") (name "Net-(LED9-C)") (class "Default")
      (node (ref "LED9") (pin "K") (pinfunction "C_K") (pintype "passive"))
      (node (ref "R22") (pin "2") (pinfunction "2_2") (pintype "passive"))
    )
    (net (code "72") (name "Net-(OK1-A)") (class "Default")
      (node (ref "OK1") (pin "1") (pinfunction "A_1") (pintype "passive"))
      (node (ref "R25") (pin "2") (pinfunction "2_2") (pintype "passive"))
    )
    (net (code "73") (name "Net-(OK1-COL)") (class "Default")
      (node (ref "JP1") (pin "3") (pinfunction "3_3") (pintype "passive"))
      (node (ref "OK1") (pin "4") (pinfunction "COL_4") (pintype "passive"))
    )
    (net (code "74") (name "Net-(OK2-A)") (class "Default")
      (node (ref "OK2") (pin "1") (pinfunction "A_1") (pintype "passive"))
      (node (ref "R26") (pin "2") (pinfunction "2_2") (pintype "passive"))
    )
    (net (code "75") (name "Net-(OK2-COL)") (class "Default")
      (node (ref "JP1") (pin "2") (pinfunction "2_2") (pintype "passive"))
      (node (ref "OK2") (pin "4") (pinfunction "COL_4") (pintype "passive"))
    )
    (net (code "76") (name "Net-(R25-Pad1)") (class "Default")
      (node (ref "R25") (pin "1") (pinfunction "1_1") (pintype "passive"))
      (node (ref "U$1") (pin "GP26_A0") (pinfunction "GP26_A0_GP26_A0") (pintype "bidirectional"))
    )
    (net (code "77") (name "Net-(R26-Pad1)") (class "Default")
      (node (ref "R26") (pin "1") (pinfunction "1_1") (pintype "passive"))
      (node (ref "U$1") (pin "GP22") (pinfunction "GP22_GP22") (pintype "bidirectional"))
    )
    (net (code "78") (name "unconnected-(U$1-GND-PadGND@5)") (class "Default")
      (node (ref "U$1") (pin "GND@5") (pinfunction "GND_GND@5") (pintype "bidirectional"))
    )
    (net (code "79") (name "unconnected-(U$1-Pad3V3)") (class "Default")
      (node (ref "U$1") (pin "3V3") (pinfunction "3V3_3V3") (pintype "bidirectional"))
    )
    (net (code "80") (name "unconnected-(U$1-Pad3V3_EN)") (class "Default")
      (node (ref "U$1") (pin "3V3_EN") (pinfunction "3V3_EN_3V3_EN") (pintype "bidirectional"))
    )
    (net (code "81") (name "unconnected-(U$1-PadADC_VREF)") (class "Default")
      (node (ref "U$1") (pin "ADC_VREF") (pinfunction "ADC_VREF_ADC_VREF") (pintype "bidirectional"))
    )
    (net (code "82") (name "unconnected-(U$1-PadGP28_A2)") (class "Default")
      (node (ref "U$1") (pin "GP28_A2") (pinfunction "GP28_A2_GP28_A2") (pintype "bidirectional"))
    )
    (net (code "83") (name "unconnected-(U$1-PadRUN)") (class "Default")
      (node (ref "U$1") (pin "RUN") (pinfunction "RUN_RUN") (pintype "bidirectional"))
    )
    (net (code "84") (name "unconnected-(U$1-PadSWCLK)") (class "Default")
      (node (ref "U$1") (pin "SWCLK") (pinfunction "SWCLK_SWCLK") (pintype "bidirectional"))
    )
    (net (code "85") (name "unconnected-(U$1-PadSWDIO)") (class "Default")
      (node (ref "U$1") (pin "SWDIO") (pinfunction "SWDIO_SWDIO") (pintype "bidirectional"))
    )
    (net (code "86") (name "unconnected-(U$1-PadVBUS)") (class "Default")
      (node (ref "U$1") (pin "VBUS") (pinfunction "VBUS_VBUS") (pintype "bidirectional"))
    )
  )
)
